# STM32_Input_Conditioning.net
KiCad netlist of a schematic drawn in Altium Designer
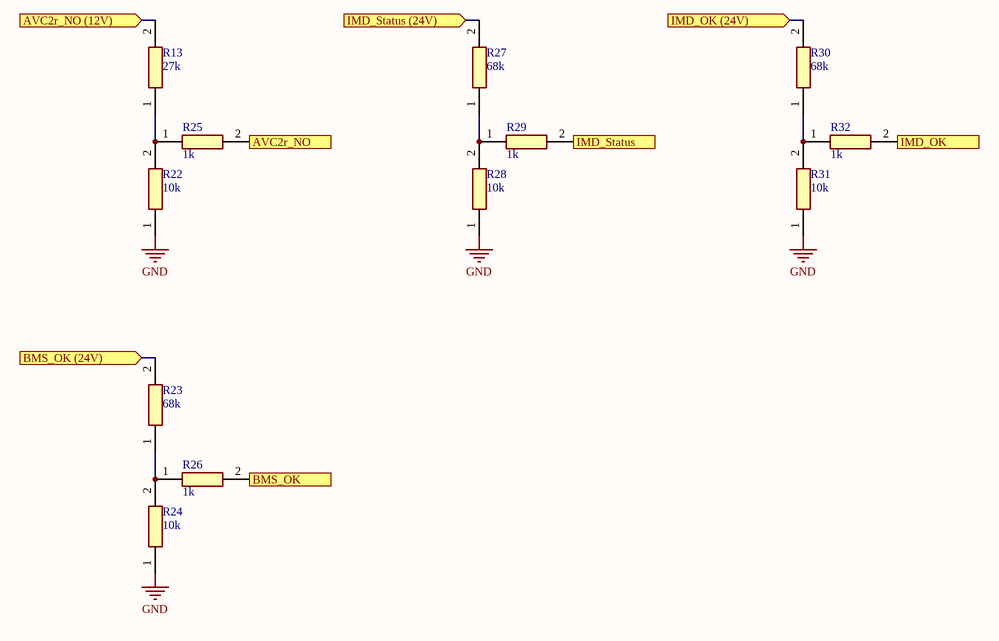
[diagram p0: STM32 Input Conditioning.SchDoc]

(export (version "E")
  (design (tool "Eeschema 10.0.6"))
  (components
    (comp (ref "R13")
      (value "27k")
      (footprint "SamacSys:RESC1608X55N")
      (description "Resistor")
      (fields
        (field (name "MANUFACTURER_PART_NUMBER") "TNPW060327K0BEEA")
        (field (name "MOUSER PART NUMBER") "71-TNPW060327K0BEEA")
      )
      (libsource (lib "*") (part "TNPW060327K0BEEA"))
    )
    (comp (ref "R22")
      (value "10k")
      (footprint "SamacSys:RESC1608X55N")
      (description "Resistor")
      (fields
        (field (name "MANUFACTURER_PART_NUMBER") "CRGCQ0603F10K")
        (field (name "MOUSER PART NUMBER") "279-CRGCQ0603F10K")
      )
      (libsource (lib "*") (part "CRGCQ0603F10K"))
    )
    (comp (ref "R23")
      (value "68k")
      (footprint "SamacSys:RESC1608X55N")
      (description "Resistor")
      (fields (field (name "MANUFACTURER_PART_NUMBER") "MCT06030D6802BP500"))
      (libsource (lib "*") (part "MCT06030D6802BP500"))
    )
    (comp (ref "R24")
      (value "10k")
      (footprint "SamacSys:RESC1608X55N")
      (description "Resistor")
      (fields
        (field (name "MANUFACTURER_PART_NUMBER") "CRGCQ0603F10K")
        (field (name "MOUSER PART NUMBER") "279-CRGCQ0603F10K")
      )
      (libsource (lib "*") (part "CRGCQ0603F10K"))
    )
    (comp (ref "R25")
      (value "1k")
      (footprint "SamacSys:RESC1608X55N")
      (description "Resistor")
      (fields
        (field (name "MANUFACTURER_PART_NUMBER") "RMCF0603JT1K00")
        (field (name "MOUSER PART NUMBER") "708-RMCF0603JT1K00")
      )
      (libsource (lib "*") (part "RMCF0603JT1K00"))
    )
    (comp (ref "R26")
      (value "1k")
      (footprint "SamacSys:RESC1608X55N")
      (description "Resistor")
      (fields
        (field (name "MANUFACTURER_PART_NUMBER") "RMCF0603JT1K00")
        (field (name "MOUSER PART NUMBER") "708-RMCF0603JT1K00")
      )
      (libsource (lib "*") (part "RMCF0603JT1K00"))
    )
    (comp (ref "R27")
      (value "68k")
      (footprint "SamacSys:RESC1608X55N")
      (description "Resistor")
      (fields (field (name "MANUFACTURER_PART_NUMBER") "MCT06030D6802BP500"))
      (libsource (lib "*") (part "MCT06030D6802BP500"))
    )
    (comp (ref "R28")
      (value "10k")
      (footprint "SamacSys:RESC1608X55N")
      (description "Resistor")
      (fields
        (field (name "MANUFACTURER_PART_NUMBER") "CRGCQ0603F10K")
        (field (name "MOUSER PART NUMBER") "279-CRGCQ0603F10K")
      )
      (libsource (lib "*") (part "CRGCQ0603F10K"))
    )
    (comp (ref "R29")
      (value "1k")
      (footprint "SamacSys:RESC1608X55N")
      (description "Resistor")
      (fields
        (field (name "MANUFACTURER_PART_NUMBER") "RMCF0603JT1K00")
        (field (name "MOUSER PART NUMBER") "708-RMCF0603JT1K00")
      )
      (libsource (lib "*") (part "RMCF0603JT1K00"))
    )
    (comp (ref "R30")
      (value "68k")
      (footprint "SamacSys:RESC1608X55N")
      (description "Resistor")
      (fields (field (name "MANUFACTURER_PART_NUMBER") "MCT06030D6802BP500"))
      (libsource (lib "*") (part "MCT06030D6802BP500"))
    )
    (comp (ref "R31")
      (value "10k")
      (footprint "SamacSys:RESC1608X55N")
      (description "Resistor")
      (fields
        (field (name "MANUFACTURER_PART_NUMBER") "CRGCQ0603F10K")
        (field (name "MOUSER PART NUMBER") "279-CRGCQ0603F10K")
      )
      (libsource (lib "*") (part "CRGCQ0603F10K"))
    )
    (comp (ref "R32")
      (value "1k")
      (footprint "SamacSys:RESC1608X55N")
      (description "Resistor")
      (fields
        (field (name "MANUFACTURER_PART_NUMBER") "RMCF0603JT1K00")
        (field (name "MOUSER PART NUMBER") "708-RMCF0603JT1K00")
      )
      (libsource (lib "*") (part "RMCF0603JT1K00"))
    )
  )
  (nets
    (net (code "1") (name "/AVC2r_NO") (class "Default")
      (node (ref "R25") (pin "2") (pinfunction "2_2") (pintype "passive"))
    )
    (net (code "2") (name "/AVC2r_NO (12V)") (class "Default")
      (node (ref "R13") (pin "2") (pinfunction "2_2") (pintype "passive"))
    )
    (net (code "3") (name "/BMS_OK") (class "Default")
      (node (ref "R26") (pin "2") (pinfunction "2_2") (pintype "passive"))
    )
    (net (code "4") (name "/BMS_OK (24V)") (class "Default")
      (node (ref "R23") (pin "2") (pinfunction "2_2") (pintype "passive"))
    )
    (net (code "5") (name "/IMD_OK") (class "Default")
      (node (ref "R32") (pin "2") (pinfunction "2_2") (pintype "passive"))
    )
    (net (code "6") (name "/IMD_OK (24V)") (class "Default")
      (node (ref "R30") (pin "2") (pinfunction "2_2") (pintype "passive"))
    )
    (net (code "7") (name "/IMD_Status") (class "Default")
      (node (ref "R29") (pin "2") (pinfunction "2_2") (pintype "passive"))
    )
    (net (code "8") (name "/IMD_Status (24V)") (class "Default")
      (node (ref "R27") (pin "2") (pinfunction "2_2") (pintype "passive"))
    )
    (net (code "9") (name "GND") (class "Default")
      (node (ref "R22") (pin "1") (pinfunction "1_1") (pintype "passive"))
      (node (ref "R24") (pin "1") (pinfunction "1_1") (pintype "passive"))
      (node (ref "R28") (pin "1") (pinfunction "1_1") (pintype "passive"))
      (node (ref "R31") (pin "1") (pinfunction "1_1") (pintype "passive"))
    )
    (net (code "10") (name "Net-(R13-Pad1)") (class "Default")
      (node (ref "R13") (pin "1") (pinfunction "1_1") (pintype "passive"))
      (node (ref "R22") (pin "2") (pinfunction "2_2") (pintype "passive"))
      (node (ref "R25") (pin "1") (pinfunction "1_1") (pintype "passive"))
    )
    (net (code "11") (name "Net-(R23-Pad1)") (class "Default")
      (node (ref "R23") (pin "1") (pinfunction "1_1") (pintype "passive"))
      (node (ref "R24") (pin "2") (pinfunction "2_2") (pintype "passive"))
      (node (ref "R26") (pin "1") (pinfunction "1_1") (pintype "passive"))
    )
    (net (code "12") (name "Net-(R27-Pad1)") (class "Default")
      (node (ref "R27") (pin "1") (pinfunction "1_1") (pintype "passive"))
      (node (ref "R28") (pin "2") (pinfunction "2_2") (pintype "passive"))
      (node (ref "R29") (pin "1") (pinfunction "1_1") (pintype "passive"))
    )
    (net (code "13") (name "Net-(R30-Pad1)") (class "Default")
      (node (ref "R30") (pin "1") (pinfunction "1_1") (pintype "passive"))
      (node (ref "R31") (pin "2") (pinfunction "2_2") (pintype "passive"))
      (node (ref "R32") (pin "1") (pinfunction "1_1") (pintype "passive"))
    )
  )
)
